# R151X.net
KiCad netlist of a schematic drawn in EAGLE
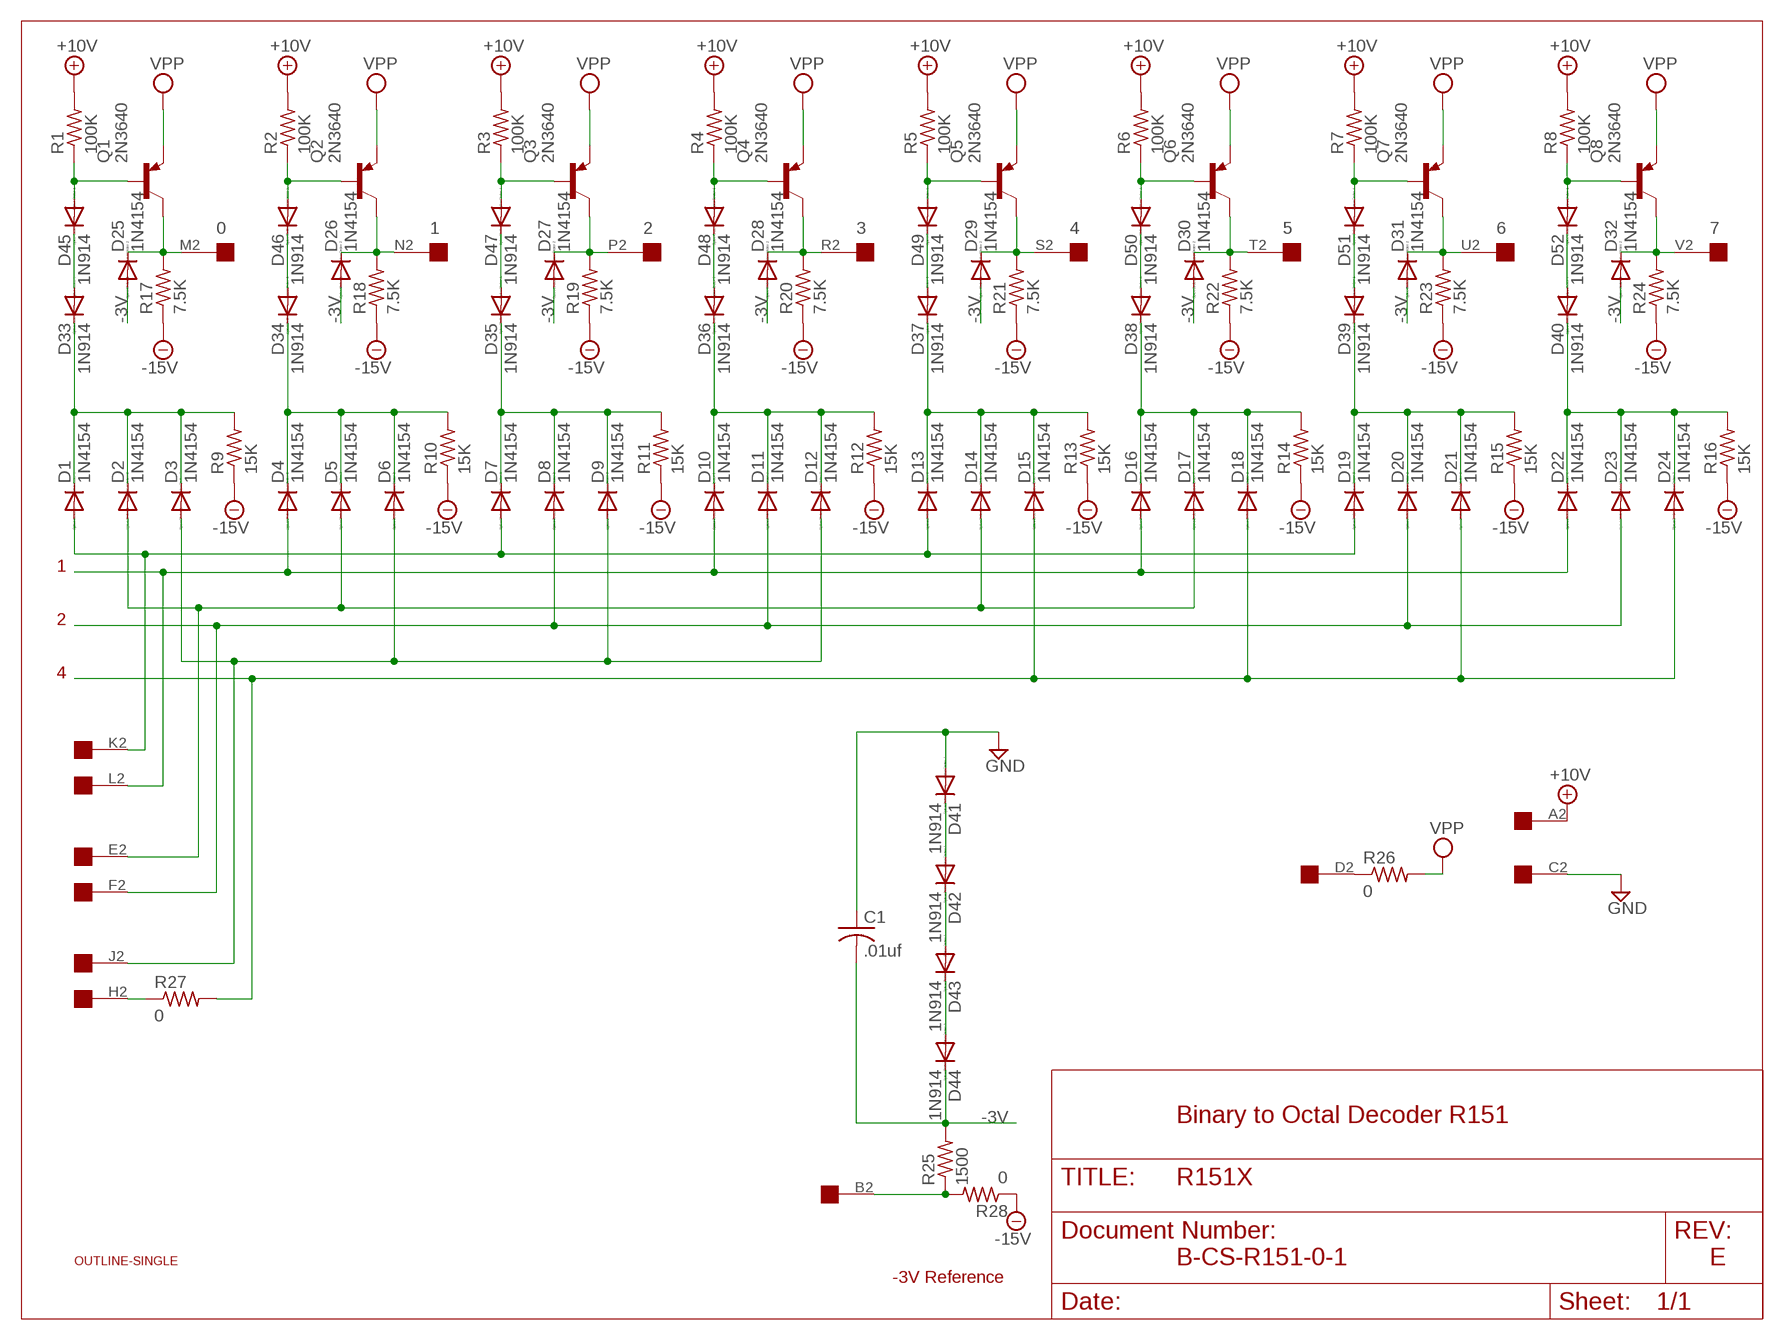
[diagram p0: schematic, sheet 1]

(export (version "E")
  (design (tool "Eeschema 10.0.6"))
  (components
    (comp (ref "C1")
      (value ".01uf")
      (footprint "eagle-import:C050-025X075")
      (libsource (lib "eagle-import") (part "C-US050-025X075"))
    )
    (comp (ref "D1")
      (value "1N4154")
      (footprint "eagle-import:DO35-10")
      (libsource (lib "eagle-import") (part "1N4148DO35-10"))
    )
    (comp (ref "D2")
      (value "1N4154")
      (footprint "eagle-import:DO35-10")
      (libsource (lib "eagle-import") (part "1N4148DO35-10"))
    )
    (comp (ref "D3")
      (value "1N4154")
      (footprint "eagle-import:DO35-10")
      (libsource (lib "eagle-import") (part "1N4148DO35-10"))
    )
    (comp (ref "D4")
      (value "1N4154")
      (footprint "eagle-import:DO35-10")
      (libsource (lib "eagle-import") (part "1N4148DO35-10"))
    )
    (comp (ref "D5")
      (value "1N4154")
      (footprint "eagle-import:DO35-10")
      (libsource (lib "eagle-import") (part "1N4148DO35-10"))
    )
    (comp (ref "D6")
      (value "1N4154")
      (footprint "eagle-import:DO35-10")
      (libsource (lib "eagle-import") (part "1N4148DO35-10"))
    )
    (comp (ref "D7")
      (value "1N4154")
      (footprint "eagle-import:DO35-10")
      (libsource (lib "eagle-import") (part "1N4148DO35-10"))
    )
    (comp (ref "D8")
      (value "1N4154")
      (footprint "eagle-import:DO35-10")
      (libsource (lib "eagle-import") (part "1N4148DO35-10"))
    )
    (comp (ref "D9")
      (value "1N4154")
      (footprint "eagle-import:DO35-10")
      (libsource (lib "eagle-import") (part "1N4148DO35-10"))
    )
    (comp (ref "D10")
      (value "1N4154")
      (footprint "eagle-import:DO35-10")
      (libsource (lib "eagle-import") (part "1N4148DO35-10"))
    )
    (comp (ref "D11")
      (value "1N4154")
      (footprint "eagle-import:DO35-10")
      (libsource (lib "eagle-import") (part "1N4148DO35-10"))
    )
    (comp (ref "D12")
      (value "1N4154")
      (footprint "eagle-import:DO35-10")
      (libsource (lib "eagle-import") (part "1N4148DO35-10"))
    )
    (comp (ref "D13")
      (value "1N4154")
      (footprint "eagle-import:DO35-10")
      (libsource (lib "eagle-import") (part "1N4148DO35-10"))
    )
    (comp (ref "D14")
      (value "1N4154")
      (footprint "eagle-import:DO35-10")
      (libsource (lib "eagle-import") (part "1N4148DO35-10"))
    )
    (comp (ref "D15")
      (value "1N4154")
      (footprint "eagle-import:DO35-10")
      (libsource (lib "eagle-import") (part "1N4148DO35-10"))
    )
    (comp (ref "D16")
      (value "1N4154")
      (footprint "eagle-import:DO35-10")
      (libsource (lib "eagle-import") (part "1N4148DO35-10"))
    )
    (comp (ref "D17")
      (value "1N4154")
      (footprint "eagle-import:DO35-10")
      (libsource (lib "eagle-import") (part "1N4148DO35-10"))
    )
    (comp (ref "D18")
      (value "1N4154")
      (footprint "eagle-import:DO35-10")
      (libsource (lib "eagle-import") (part "1N4148DO35-10"))
    )
    (comp (ref "D19")
      (value "1N4154")
      (footprint "eagle-import:DO35-10")
      (libsource (lib "eagle-import") (part "1N4148DO35-10"))
    )
    (comp (ref "D20")
      (value "1N4154")
      (footprint "eagle-import:DO35-10")
      (libsource (lib "eagle-import") (part "1N4148DO35-10"))
    )
    (comp (ref "D21")
      (value "1N4154")
      (footprint "eagle-import:DO35-10")
      (libsource (lib "eagle-import") (part "1N4148DO35-10"))
    )
    (comp (ref "D22")
      (value "1N4154")
      (footprint "eagle-import:DO35-10")
      (libsource (lib "eagle-import") (part "1N4148DO35-10"))
    )
    (comp (ref "D23")
      (value "1N4154")
      (footprint "eagle-import:DO35-10")
      (libsource (lib "eagle-import") (part "1N4148DO35-10"))
    )
    (comp (ref "D24")
      (value "1N4154")
      (footprint "eagle-import:DO35-10")
      (libsource (lib "eagle-import") (part "1N4148DO35-10"))
    )
    (comp (ref "D25")
      (value "1N4154")
      (footprint "eagle-import:DO35-10")
      (libsource (lib "eagle-import") (part "1N4148DO35-10"))
    )
    (comp (ref "D26")
      (value "1N4154")
      (footprint "eagle-import:DO35-10")
      (libsource (lib "eagle-import") (part "1N4148DO35-10"))
    )
    (comp (ref "D27")
      (value "1N4154")
      (footprint "eagle-import:DO35-10")
      (libsource (lib "eagle-import") (part "1N4148DO35-10"))
    )
    (comp (ref "D28")
      (value "1N4154")
      (footprint "eagle-import:DO35-10")
      (libsource (lib "eagle-import") (part "1N4148DO35-10"))
    )
    (comp (ref "D29")
      (value "1N4154")
      (footprint "eagle-import:DO35-10")
      (libsource (lib "eagle-import") (part "1N4148DO35-10"))
    )
    (comp (ref "D30")
      (value "1N4154")
      (footprint "eagle-import:DO35-10")
      (libsource (lib "eagle-import") (part "1N4148DO35-10"))
    )
    (comp (ref "D31")
      (value "1N4154")
      (footprint "eagle-import:DO35-10")
      (libsource (lib "eagle-import") (part "1N4148DO35-10"))
    )
    (comp (ref "D32")
      (value "1N4154")
      (footprint "eagle-import:DO35-10")
      (libsource (lib "eagle-import") (part "1N4148DO35-10"))
    )
    (comp (ref "D33")
      (value "1N914")
      (footprint "eagle-import:DO35-10")
      (libsource (lib "eagle-import") (part "1N4148DO35-10"))
    )
    (comp (ref "D34")
      (value "1N914")
      (footprint "eagle-import:DO35-10")
      (libsource (lib "eagle-import") (part "1N4148DO35-10"))
    )
    (comp (ref "D35")
      (value "1N914")
      (footprint "eagle-import:DO35-10")
      (libsource (lib "eagle-import") (part "1N4148DO35-10"))
    )
    (comp (ref "D36")
      (value "1N914")
      (footprint "eagle-import:DO35-10")
      (libsource (lib "eagle-import") (part "1N4148DO35-10"))
    )
    (comp (ref "D37")
      (value "1N914")
      (footprint "eagle-import:DO35-10")
      (libsource (lib "eagle-import") (part "1N4148DO35-10"))
    )
    (comp (ref "D38")
      (value "1N914")
      (footprint "eagle-import:DO35-10")
      (libsource (lib "eagle-import") (part "1N4148DO35-10"))
    )
    (comp (ref "D39")
      (value "1N914")
      (footprint "eagle-import:DO35-10")
      (libsource (lib "eagle-import") (part "1N4148DO35-10"))
    )
    (comp (ref "D40")
      (value "1N914")
      (footprint "eagle-import:DO35-10")
      (libsource (lib "eagle-import") (part "1N4148DO35-10"))
    )
    (comp (ref "D41")
      (value "1N914")
      (footprint "eagle-import:DO35-10")
      (libsource (lib "eagle-import") (part "1N4148DO35-10"))
    )
    (comp (ref "D42")
      (value "1N914")
      (footprint "eagle-import:DO35-10")
      (libsource (lib "eagle-import") (part "1N4148DO35-10"))
    )
    (comp (ref "D43")
      (value "1N914")
      (footprint "eagle-import:DO35-10")
      (libsource (lib "eagle-import") (part "1N4148DO35-10"))
    )
    (comp (ref "D44")
      (value "1N914")
      (footprint "eagle-import:DO35-10")
      (libsource (lib "eagle-import") (part "1N4148DO35-10"))
    )
    (comp (ref "D45")
      (value "1N914")
      (footprint "eagle-import:DO35-10")
      (libsource (lib "eagle-import") (part "1N4148DO35-10"))
    )
    (comp (ref "D46")
      (value "1N914")
      (footprint "eagle-import:DO35-10")
      (libsource (lib "eagle-import") (part "1N4148DO35-10"))
    )
    (comp (ref "D47")
      (value "1N914")
      (footprint "eagle-import:DO35-10")
      (libsource (lib "eagle-import") (part "1N4148DO35-10"))
    )
    (comp (ref "D48")
      (value "1N914")
      (footprint "eagle-import:DO35-10")
      (libsource (lib "eagle-import") (part "1N4148DO35-10"))
    )
    (comp (ref "D49")
      (value "1N914")
      (footprint "eagle-import:DO35-10")
      (libsource (lib "eagle-import") (part "1N4148DO35-10"))
    )
    (comp (ref "D50")
      (value "1N914")
      (footprint "eagle-import:DO35-10")
      (libsource (lib "eagle-import") (part "1N4148DO35-10"))
    )
    (comp (ref "D51")
      (value "1N914")
      (footprint "eagle-import:DO35-10")
      (libsource (lib "eagle-import") (part "1N4148DO35-10"))
    )
    (comp (ref "D52")
      (value "1N914")
      (footprint "eagle-import:DO35-10")
      (libsource (lib "eagle-import") (part "1N4148DO35-10"))
    )
    (comp (ref "Q1")
      (value "2N3640")
      (footprint "eagle-import:TO39")
      (libsource (lib "eagle-import") (part "2N3637"))
    )
    (comp (ref "Q2")
      (value "2N3640")
      (footprint "eagle-import:TO39")
      (libsource (lib "eagle-import") (part "2N3637"))
    )
    (comp (ref "Q3")
      (value "2N3640")
      (footprint "eagle-import:TO39")
      (libsource (lib "eagle-import") (part "2N3637"))
    )
    (comp (ref "Q4")
      (value "2N3640")
      (footprint "eagle-import:TO39")
      (libsource (lib "eagle-import") (part "2N3637"))
    )
    (comp (ref "Q5")
      (value "2N3640")
      (footprint "eagle-import:TO39")
      (libsource (lib "eagle-import") (part "2N3637"))
    )
    (comp (ref "Q6")
      (value "2N3640")
      (footprint "eagle-import:TO39")
      (libsource (lib "eagle-import") (part "2N3637"))
    )
    (comp (ref "Q7")
      (value "2N3640")
      (footprint "eagle-import:TO39")
      (libsource (lib "eagle-import") (part "2N3637"))
    )
    (comp (ref "Q8")
      (value "2N3640")
      (footprint "eagle-import:TO39")
      (libsource (lib "eagle-import") (part "2N3637"))
    )
    (comp (ref "R1")
      (value "100K")
      (footprint "eagle-import:0207_10")
      (libsource (lib "eagle-import") (part "R-US_0207/10"))
    )
    (comp (ref "R2")
      (value "100K")
      (footprint "eagle-import:0207_10")
      (libsource (lib "eagle-import") (part "R-US_0207/10"))
    )
    (comp (ref "R3")
      (value "100K")
      (footprint "eagle-import:0207_10")
      (libsource (lib "eagle-import") (part "R-US_0207/10"))
    )
    (comp (ref "R4")
      (value "100K")
      (footprint "eagle-import:0207_10")
      (libsource (lib "eagle-import") (part "R-US_0207/10"))
    )
    (comp (ref "R5")
      (value "100K")
      (footprint "eagle-import:0207_10")
      (libsource (lib "eagle-import") (part "R-US_0207/10"))
    )
    (comp (ref "R6")
      (value "100K")
      (footprint "eagle-import:0207_10")
      (libsource (lib "eagle-import") (part "R-US_0207/10"))
    )
    (comp (ref "R7")
      (value "100K")
      (footprint "eagle-import:0207_10")
      (libsource (lib "eagle-import") (part "R-US_0207/10"))
    )
    (comp (ref "R8")
      (value "100K")
      (footprint "eagle-import:0207_10")
      (libsource (lib "eagle-import") (part "R-US_0207/10"))
    )
    (comp (ref "R9")
      (value "15K")
      (footprint "eagle-import:0207_10")
      (libsource (lib "eagle-import") (part "R-US_0207/10"))
    )
    (comp (ref "R10")
      (value "15K")
      (footprint "eagle-import:0207_10")
      (libsource (lib "eagle-import") (part "R-US_0207/10"))
    )
    (comp (ref "R11")
      (value "15K")
      (footprint "eagle-import:0207_10")
      (libsource (lib "eagle-import") (part "R-US_0207/10"))
    )
    (comp (ref "R12")
      (value "15K")
      (footprint "eagle-import:0207_10")
      (libsource (lib "eagle-import") (part "R-US_0207/10"))
    )
    (comp (ref "R13")
      (value "15K")
      (footprint "eagle-import:0207_10")
      (libsource (lib "eagle-import") (part "R-US_0207/10"))
    )
    (comp (ref "R14")
      (value "15K")
      (footprint "eagle-import:0207_10")
      (libsource (lib "eagle-import") (part "R-US_0207/10"))
    )
    (comp (ref "R15")
      (value "15K")
      (footprint "eagle-import:0207_10")
      (libsource (lib "eagle-import") (part "R-US_0207/10"))
    )
    (comp (ref "R16")
      (value "15K")
      (footprint "eagle-import:0207_10")
      (libsource (lib "eagle-import") (part "R-US_0207/10"))
    )
    (comp (ref "R17")
      (value "7.5K")
      (footprint "eagle-import:0207_10")
      (libsource (lib "eagle-import") (part "R-US_0207/10"))
    )
    (comp (ref "R18")
      (value "7.5K")
      (footprint "eagle-import:0207_10")
      (libsource (lib "eagle-import") (part "R-US_0207/10"))
    )
    (comp (ref "R19")
      (value "7.5K")
      (footprint "eagle-import:0207_10")
      (libsource (lib "eagle-import") (part "R-US_0207/10"))
    )
    (comp (ref "R20")
      (value "7.5K")
      (footprint "eagle-import:0207_10")
      (libsource (lib "eagle-import") (part "R-US_0207/10"))
    )
    (comp (ref "R21")
      (value "7.5K")
      (footprint "eagle-import:0207_10")
      (libsource (lib "eagle-import") (part "R-US_0207/10"))
    )
    (comp (ref "R22")
      (value "7.5K")
      (footprint "eagle-import:0207_10")
      (libsource (lib "eagle-import") (part "R-US_0207/10"))
    )
    (comp (ref "R23")
      (value "7.5K")
      (footprint "eagle-import:0207_10")
      (libsource (lib "eagle-import") (part "R-US_0207/10"))
    )
    (comp (ref "R24")
      (value "7.5K")
      (footprint "eagle-import:0207_10")
      (libsource (lib "eagle-import") (part "R-US_0207/10"))
    )
    (comp (ref "R25")
      (value "1500")
      (footprint "eagle-import:0207_10")
      (libsource (lib "eagle-import") (part "R-US_0207/10"))
    )
    (comp (ref "R26")
      (value "0")
      (footprint "eagle-import:0207_10")
      (libsource (lib "eagle-import") (part "R-US_0207/10"))
    )
    (comp (ref "R27")
      (value "0")
      (footprint "eagle-import:0207_10")
      (libsource (lib "eagle-import") (part "R-US_0207/10"))
    )
    (comp (ref "R28")
      (value "0")
      (footprint "eagle-import:0207_10")
      (libsource (lib "eagle-import") (part "R-US_0207/10"))
    )
    (comp (ref "U$1")
      (value "OUTLINE-SINGLE")
      (footprint "eagle-import:SINGLE")
      (libsource (lib "eagle-import") (part "OUTLINE-SINGLE"))
    )
    (comp (ref "U$2")
      (value "EDGE-1")
      (footprint "eagle-import:EDGE-CON1")
      (libsource (lib "eagle-import") (part "EDGE-1"))
    )
  )
  (nets
    (net (code "1") (name "+10V") (class "Default")
      (node (ref "R1") (pin "2") (pinfunction "2_2") (pintype "passive"))
      (node (ref "R2") (pin "2") (pinfunction "2_2") (pintype "passive"))
      (node (ref "R3") (pin "2") (pinfunction "2_2") (pintype "passive"))
      (node (ref "R4") (pin "2") (pinfunction "2_2") (pintype "passive"))
      (node (ref "R5") (pin "2") (pinfunction "2_2") (pintype "passive"))
      (node (ref "R6") (pin "2") (pinfunction "2_2") (pintype "passive"))
      (node (ref "R7") (pin "2") (pinfunction "2_2") (pintype "passive"))
      (node (ref "R8") (pin "2") (pinfunction "2_2") (pintype "passive"))
      (node (ref "U$2") (pin "A2") (pinfunction "1_A2") (pintype "bidirectional"))
    )
    (net (code "2") (name "-15V") (class "Default")
      (node (ref "R10") (pin "1") (pinfunction "1_1") (pintype "passive"))
      (node (ref "R11") (pin "1") (pinfunction "1_1") (pintype "passive"))
      (node (ref "R12") (pin "1") (pinfunction "1_1") (pintype "passive"))
      (node (ref "R13") (pin "1") (pinfunction "1_1") (pintype "passive"))
      (node (ref "R14") (pin "1") (pinfunction "1_1") (pintype "passive"))
      (node (ref "R15") (pin "1") (pinfunction "1_1") (pintype "passive"))
      (node (ref "R16") (pin "1") (pinfunction "1_1") (pintype "passive"))
      (node (ref "R17") (pin "1") (pinfunction "1_1") (pintype "passive"))
      (node (ref "R18") (pin "1") (pinfunction "1_1") (pintype "passive"))
      (node (ref "R19") (pin "1") (pinfunction "1_1") (pintype "passive"))
      (node (ref "R20") (pin "1") (pinfunction "1_1") (pintype "passive"))
      (node (ref "R21") (pin "1") (pinfunction "1_1") (pintype "passive"))
      (node (ref "R22") (pin "1") (pinfunction "1_1") (pintype "passive"))
      (node (ref "R23") (pin "1") (pinfunction "1_1") (pintype "passive"))
      (node (ref "R24") (pin "1") (pinfunction "1_1") (pintype "passive"))
      (node (ref "R28") (pin "1") (pinfunction "1_1") (pintype "passive"))
      (node (ref "R9") (pin "1") (pinfunction "1_1") (pintype "passive"))
    )
    (net (code "3") (name "/-3V") (class "Default")
      (node (ref "C1") (pin "2") (pinfunction "2_2") (pintype "passive"))
      (node (ref "D25") (pin "A") (pinfunction "A_A") (pintype "passive"))
      (node (ref "D26") (pin "A") (pinfunction "A_A") (pintype "passive"))
      (node (ref "D27") (pin "A") (pinfunction "A_A") (pintype "passive"))
      (node (ref "D28") (pin "A") (pinfunction "A_A") (pintype "passive"))
      (node (ref "D29") (pin "A") (pinfunction "A_A") (pintype "passive"))
      (node (ref "D30") (pin "A") (pinfunction "A_A") (pintype "passive"))
      (node (ref "D31") (pin "A") (pinfunction "A_A") (pintype "passive"))
      (node (ref "D32") (pin "A") (pinfunction "A_A") (pintype "passive"))
      (node (ref "D44") (pin "C") (pinfunction "C_C") (pintype "passive"))
      (node (ref "R25") (pin "2") (pinfunction "2_2") (pintype "passive"))
    )
    (net (code "4") (name "/0") (class "Default")
      (node (ref "D25") (pin "C") (pinfunction "C_C") (pintype "passive"))
      (node (ref "Q1") (pin "3") (pinfunction "C_3") (pintype "passive"))
      (node (ref "R17") (pin "2") (pinfunction "2_2") (pintype "passive"))
      (node (ref "U$2") (pin "M2") (pinfunction "1_M2") (pintype "bidirectional"))
    )
    (net (code "5") (name "/1") (class "Default")
      (node (ref "D26") (pin "C") (pinfunction "C_C") (pintype "passive"))
      (node (ref "Q2") (pin "3") (pinfunction "C_3") (pintype "passive"))
      (node (ref "R18") (pin "2") (pinfunction "2_2") (pintype "passive"))
      (node (ref "U$2") (pin "N2") (pinfunction "1_N2") (pintype "bidirectional"))
    )
    (net (code "6") (name "/2") (class "Default")
      (node (ref "D27") (pin "C") (pinfunction "C_C") (pintype "passive"))
      (node (ref "Q3") (pin "3") (pinfunction "C_3") (pintype "passive"))
      (node (ref "R19") (pin "2") (pinfunction "2_2") (pintype "passive"))
      (node (ref "U$2") (pin "P2") (pinfunction "1_P2") (pintype "bidirectional"))
    )
    (net (code "7") (name "/3") (class "Default")
      (node (ref "D28") (pin "C") (pinfunction "C_C") (pintype "passive"))
      (node (ref "Q4") (pin "3") (pinfunction "C_3") (pintype "passive"))
      (node (ref "R20") (pin "2") (pinfunction "2_2") (pintype "passive"))
      (node (ref "U$2") (pin "R2") (pinfunction "1_R2") (pintype "bidirectional"))
    )
    (net (code "8") (name "/4") (class "Default")
      (node (ref "D29") (pin "C") (pinfunction "C_C") (pintype "passive"))
      (node (ref "Q5") (pin "3") (pinfunction "C_3") (pintype "passive"))
      (node (ref "R21") (pin "2") (pinfunction "2_2") (pintype "passive"))
      (node (ref "U$2") (pin "S2") (pinfunction "1_S2") (pintype "bidirectional"))
    )
    (net (code "9") (name "/5") (class "Default")
      (node (ref "D30") (pin "C") (pinfunction "C_C") (pintype "passive"))
      (node (ref "Q6") (pin "3") (pinfunction "C_3") (pintype "passive"))
      (node (ref "R22") (pin "2") (pinfunction "2_2") (pintype "passive"))
      (node (ref "U$2") (pin "T2") (pinfunction "1_T2") (pintype "bidirectional"))
    )
    (net (code "10") (name "/6") (class "Default")
      (node (ref "D31") (pin "C") (pinfunction "C_C") (pintype "passive"))
      (node (ref "Q7") (pin "3") (pinfunction "C_3") (pintype "passive"))
      (node (ref "R23") (pin "2") (pinfunction "2_2") (pintype "passive"))
      (node (ref "U$2") (pin "U2") (pinfunction "1_U2") (pintype "bidirectional"))
    )
    (net (code "11") (name "/7") (class "Default")
      (node (ref "D32") (pin "C") (pinfunction "C_C") (pintype "passive"))
      (node (ref "Q8") (pin "3") (pinfunction "C_3") (pintype "passive"))
      (node (ref "R24") (pin "2") (pinfunction "2_2") (pintype "passive"))
      (node (ref "U$2") (pin "V2") (pinfunction "1_V2") (pintype "bidirectional"))
    )
    (net (code "12") (name "GND") (class "Default")
      (node (ref "C1") (pin "1") (pinfunction "1_1") (pintype "passive"))
      (node (ref "D41") (pin "A") (pinfunction "A_A") (pintype "passive"))
      (node (ref "U$2") (pin "C2") (pinfunction "1_C2") (pintype "bidirectional"))
    )
    (net (code "13") (name "Net-(D1-PadC)") (class "Default")
      (node (ref "D1") (pin "C") (pinfunction "C_C") (pintype "passive"))
      (node (ref "D2") (pin "C") (pinfunction "C_C") (pintype "passive"))
      (node (ref "D3") (pin "C") (pinfunction "C_C") (pintype "passive"))
      (node (ref "D33") (pin "C") (pinfunction "C_C") (pintype "passive"))
      (node (ref "R9") (pin "2") (pinfunction "2_2") (pintype "passive"))
    )
    (net (code "14") (name "Net-(D10-PadC)") (class "Default")
      (node (ref "D10") (pin "C") (pinfunction "C_C") (pintype "passive"))
      (node (ref "D11") (pin "C") (pinfunction "C_C") (pintype "passive"))
      (node (ref "D12") (pin "C") (pinfunction "C_C") (pintype "passive"))
      (node (ref "D36") (pin "C") (pinfunction "C_C") (pintype "passive"))
      (node (ref "R12") (pin "2") (pinfunction "2_2") (pintype "passive"))
    )
    (net (code "15") (name "Net-(D13-PadC)") (class "Default")
      (node (ref "D13") (pin "C") (pinfunction "C_C") (pintype "passive"))
      (node (ref "D14") (pin "C") (pinfunction "C_C") (pintype "passive"))
      (node (ref "D15") (pin "C") (pinfunction "C_C") (pintype "passive"))
      (node (ref "D37") (pin "C") (pinfunction "C_C") (pintype "passive"))
      (node (ref "R13") (pin "2") (pinfunction "2_2") (pintype "passive"))
    )
    (net (code "16") (name "Net-(D15-PadA)") (class "Default")
      (node (ref "D15") (pin "A") (pinfunction "A_A") (pintype "passive"))
      (node (ref "D18") (pin "A") (pinfunction "A_A") (pintype "passive"))
      (node (ref "D21") (pin "A") (pinfunction "A_A") (pintype "passive"))
      (node (ref "D24") (pin "A") (pinfunction "A_A") (pintype "passive"))
      (node (ref "R27") (pin "2") (pinfunction "2_2") (pintype "passive"))
    )
    (net (code "17") (name "Net-(D16-PadC)") (class "Default")
      (node (ref "D16") (pin "C") (pinfunction "C_C") (pintype "passive"))
      (node (ref "D17") (pin "C") (pinfunction "C_C") (pintype "passive"))
      (node (ref "D18") (pin "C") (pinfunction "C_C") (pintype "passive"))
      (node (ref "D38") (pin "C") (pinfunction "C_C") (pintype "passive"))
      (node (ref "R14") (pin "2") (pinfunction "2_2") (pintype "passive"))
    )
    (net (code "18") (name "Net-(D19-PadC)") (class "Default")
      (node (ref "D19") (pin "C") (pinfunction "C_C") (pintype "passive"))
      (node (ref "D20") (pin "C") (pinfunction "C_C") (pintype "passive"))
      (node (ref "D21") (pin "C") (pinfunction "C_C") (pintype "passive"))
      (node (ref "D39") (pin "C") (pinfunction "C_C") (pintype "passive"))
      (node (ref "R15") (pin "2") (pinfunction "2_2") (pintype "passive"))
    )
    (net (code "19") (name "Net-(D22-PadC)") (class "Default")
      (node (ref "D22") (pin "C") (pinfunction "C_C") (pintype "passive"))
      (node (ref "D23") (pin "C") (pinfunction "C_C") (pintype "passive"))
      (node (ref "D24") (pin "C") (pinfunction "C_C") (pintype "passive"))
      (node (ref "D40") (pin "C") (pinfunction "C_C") (pintype "passive"))
      (node (ref "R16") (pin "2") (pinfunction "2_2") (pintype "passive"))
    )
    (net (code "20") (name "Net-(D33-PadA)") (class "Default")
      (node (ref "D33") (pin "A") (pinfunction "A_A") (pintype "passive"))
      (node (ref "D45") (pin "C") (pinfunction "C_C") (pintype "passive"))
    )
    (net (code "21") (name "Net-(D34-PadA)") (class "Default")
      (node (ref "D34") (pin "A") (pinfunction "A_A") (pintype "passive"))
      (node (ref "D46") (pin "C") (pinfunction "C_C") (pintype "passive"))
    )
    (net (code "22") (name "Net-(D34-PadC)") (class "Default")
      (node (ref "D34") (pin "C") (pinfunction "C_C") (pintype "passive"))
      (node (ref "D4") (pin "C") (pinfunction "C_C") (pintype "passive"))
      (node (ref "D5") (pin "C") (pinfunction "C_C") (pintype "passive"))
      (node (ref "D6") (pin "C") (pinfunction "C_C") (pintype "passive"))
      (node (ref "R10") (pin "2") (pinfunction "2_2") (pintype "passive"))
    )
    (net (code "23") (name "Net-(D35-PadA)") (class "Default")
      (node (ref "D35") (pin "A") (pinfunction "A_A") (pintype "passive"))
      (node (ref "D47") (pin "C") (pinfunction "C_C") (pintype "passive"))
    )
    (net (code "24") (name "Net-(D35-PadC)") (class "Default")
      (node (ref "D35") (pin "C") (pinfunction "C_C") (pintype "passive"))
      (node (ref "D7") (pin "C") (pinfunction "C_C") (pintype "passive"))
      (node (ref "D8") (pin "C") (pinfunction "C_C") (pintype "passive"))
      (node (ref "D9") (pin "C") (pinfunction "C_C") (pintype "passive"))
      (node (ref "R11") (pin "2") (pinfunction "2_2") (pintype "passive"))
    )
    (net (code "25") (name "Net-(D36-PadA)") (class "Default")
      (node (ref "D36") (pin "A") (pinfunction "A_A") (pintype "passive"))
      (node (ref "D48") (pin "C") (pinfunction "C_C") (pintype "passive"))
    )
    (net (code "26") (name "Net-(D37-PadA)") (class "Default")
      (node (ref "D37") (pin "A") (pinfunction "A_A") (pintype "passive"))
      (node (ref "D49") (pin "C") (pinfunction "C_C") (pintype "passive"))
    )
    (net (code "27") (name "Net-(D38-PadA)") (class "Default")
      (node (ref "D38") (pin "A") (pinfunction "A_A") (pintype "passive"))
      (node (ref "D50") (pin "C") (pinfunction "C_C") (pintype "passive"))
    )
    (net (code "28") (name "Net-(D39-PadA)") (class "Default")
      (node (ref "D39") (pin "A") (pinfunction "A_A") (pintype "passive"))
      (node (ref "D51") (pin "C") (pinfunction "C_C") (pintype "passive"))
    )
    (net (code "29") (name "Net-(D40-PadA)") (class "Default")
      (node (ref "D40") (pin "A") (pinfunction "A_A") (pintype "passive"))
      (node (ref "D52") (pin "C") (pinfunction "C_C") (pintype "passive"))
    )
    (net (code "30") (name "Net-(D41-PadC)") (class "Default")
      (node (ref "D41") (pin "C") (pinfunction "C_C") (pintype "passive"))
      (node (ref "D42") (pin "A") (pinfunction "A_A") (pintype "passive"))
    )
    (net (code "31") (name "Net-(D42-PadC)") (class "Default")
      (node (ref "D42") (pin "C") (pinfunction "C_C") (pintype "passive"))
      (node (ref "D43") (pin "A") (pinfunction "A_A") (pintype "passive"))
    )
    (net (code "32") (name "Net-(D43-PadC)") (class "Default")
      (node (ref "D43") (pin "C") (pinfunction "C_C") (pintype "passive"))
      (node (ref "D44") (pin "A") (pinfunction "A_A") (pintype "passive"))
    )
    (net (code "33") (name "Net-(Q1-B)") (class "Default")
      (node (ref "D45") (pin "A") (pinfunction "A_A") (pintype "passive"))
      (node (ref "Q1") (pin "2") (pinfunction "B_2") (pintype "passive"))
      (node (ref "R1") (pin "1") (pinfunction "1_1") (pintype "passive"))
    )
    (net (code "34") (name "Net-(Q2-B)") (class "Default")
      (node (ref "D46") (pin "A") (pinfunction "A_A") (pintype "passive"))
      (node (ref "Q2") (pin "2") (pinfunction "B_2") (pintype "passive"))
      (node (ref "R2") (pin "1") (pinfunction "1_1") (pintype "passive"))
    )
    (net (code "35") (name "Net-(Q3-B)") (class "Default")
      (node (ref "D47") (pin "A") (pinfunction "A_A") (pintype "passive"))
      (node (ref "Q3") (pin "2") (pinfunction "B_2") (pintype "passive"))
      (node (ref "R3") (pin "1") (pinfunction "1_1") (pintype "passive"))
    )
    (net (code "36") (name "Net-(Q4-B)") (class "Default")
      (node (ref "D48") (pin "A") (pinfunction "A_A") (pintype "passive"))
      (node (ref "Q4") (pin "2") (pinfunction "B_2") (pintype "passive"))
      (node (ref "R4") (pin "1") (pinfunction "1_1") (pintype "passive"))
    )
    (net (code "37") (name "Net-(Q5-B)") (class "Default")
      (node (ref "D49") (pin "A") (pinfunction "A_A") (pintype "passive"))
      (node (ref "Q5") (pin "2") (pinfunction "B_2") (pintype "passive"))
      (node (ref "R5") (pin "1") (pinfunction "1_1") (pintype "passive"))
    )
    (net (code "38") (name "Net-(Q6-B)") (class "Default")
      (node (ref "D50") (pin "A") (pinfunction "A_A") (pintype "passive"))
      (node (ref "Q6") (pin "2") (pinfunction "B_2") (pintype "passive"))
      (node (ref "R6") (pin "1") (pinfunction "1_1") (pintype "passive"))
    )
    (net (code "39") (name "Net-(Q7-B)") (class "Default")
      (node (ref "D51") (pin "A") (pinfunction "A_A") (pintype "passive"))
      (node (ref "Q7") (pin "2") (pinfunction "B_2") (pintype "passive"))
      (node (ref "R7") (pin "1") (pinfunction "1_1") (pintype "passive"))
    )
    (net (code "40") (name "Net-(Q8-B)") (class "Default")
      (node (ref "D52") (pin "A") (pinfunction "A_A") (pintype "passive"))
      (node (ref "Q8") (pin "2") (pinfunction "B_2") (pintype "passive"))
      (node (ref "R8") (pin "1") (pinfunction "1_1") (pintype "passive"))
    )
    (net (code "41") (name "Net-(U$2B-1)") (class "Default")
      (node (ref "R25") (pin "1") (pinfunction "1_1") (pintype "passive"))
      (node (ref "R28") (pin "2") (pinfunction "2_2") (pintype "passive"))
      (node (ref "U$2") (pin "B2") (pinfunction "1_B2") (pintype "bidirectional"))
    )
    (net (code "42") (name "Net-(U$2D-1)") (class "Default")
      (node (ref "R26") (pin "1") (pinfunction "1_1") (pintype "passive"))
      (node (ref "U$2") (pin "D2") (pinfunction "1_D2") (pintype "bidirectional"))
    )
    (net (code "43") (name "Net-(U$2E-1)") (class "Default")
      (node (ref "D14") (pin "A") (pinfunction "A_A") (pintype "passive"))
      (node (ref "D17") (pin "A") (pinfunction "A_A") (pintype "passive"))
      (node (ref "D2") (pin "A") (pinfunction "A_A") (pintype "passive"))
      (node (ref "D5") (pin "A") (pinfunction "A_A") (pintype "passive"))
      (node (ref "U$2") (pin "E2") (pinfunction "1_E2") (pintype "bidirectional"))
    )
    (net (code "44") (name "Net-(U$2F-1)") (class "Default")
      (node (ref "D11") (pin "A") (pinfunction "A_A") (pintype "passive"))
      (node (ref "D20") (pin "A") (pinfunction "A_A") (pintype "passive"))
      (node (ref "D23") (pin "A") (pinfunction "A_A") (pintype "passive"))
      (node (ref "D8") (pin "A") (pinfunction "A_A") (pintype "passive"))
      (node (ref "U$2") (pin "F2") (pinfunction "1_F2") (pintype "bidirectional"))
    )
    (net (code "45") (name "Net-(U$2G-1)") (class "Default")
      (node (ref "R27") (pin "1") (pinfunction "1_1") (pintype "passive"))
      (node (ref "U$2") (pin "H2") (pinfunction "1_H2") (pintype "bidirectional"))
    )
    (net (code "46") (name "Net-(U$2H-1)") (class "Default")
      (node (ref "D12") (pin "A") (pinfunction "A_A") (pintype "passive"))
      (node (ref "D3") (pin "A") (pinfunction "A_A") (pintype "passive"))
      (node (ref "D6") (pin "A") (pinfunction "A_A") (pintype "passive"))
      (node (ref "D9") (pin "A") (pinfunction "A_A") (pintype "passive"))
      (node (ref "U$2") (pin "J2") (pinfunction "1_J2") (pintype "bidirectional"))
    )
    (net (code "47") (name "Net-(U$2I-1)") (class "Default")
      (node (ref "D1") (pin "A") (pinfunction "A_A") (pintype "passive"))
      (node (ref "D13") (pin "A") (pinfunction "A_A") (pintype "passive"))
      (node (ref "D19") (pin "A") (pinfunction "A_A") (pintype "passive"))
      (node (ref "D7") (pin "A") (pinfunction "A_A") (pintype "passive"))
      (node (ref "U$2") (pin "K2") (pinfunction "1_K2") (pintype "bidirectional"))
    )
    (net (code "48") (name "Net-(U$2J-1)") (class "Default")
      (node (ref "D10") (pin "A") (pinfunction "A_A") (pintype "passive"))
      (node (ref "D16") (pin "A") (pinfunction "A_A") (pintype "passive"))
      (node (ref "D22") (pin "A") (pinfunction "A_A") (pintype "passive"))
      (node (ref "D4") (pin "A") (pinfunction "A_A") (pintype "passive"))
      (node (ref "U$2") (pin "L2") (pinfunction "1_L2") (pintype "bidirectional"))
    )
    (net (code "49") (name "VPP") (class "Default")
      (node (ref "Q1") (pin "1") (pinfunction "E_1") (pintype "passive"))
      (node (ref "Q2") (pin "1") (pinfunction "E_1") (pintype "passive"))
      (node (ref "Q3") (pin "1") (pinfunction "E_1") (pintype "passive"))
      (node (ref "Q4") (pin "1") (pinfunction "E_1") (pintype "passive"))
      (node (ref "Q5") (pin "1") (pinfunction "E_1") (pintype "passive"))
      (node (ref "Q6") (pin "1") (pinfunction "E_1") (pintype "passive"))
      (node (ref "Q7") (pin "1") (pinfunction "E_1") (pintype "passive"))
      (node (ref "Q8") (pin "1") (pinfunction "E_1") (pintype "passive"))
      (node (ref "R26") (pin "2") (pinfunction "2_2") (pintype "passive"))
    )
  )
)
